# NG2092_EEPROM.net
KiCad netlist of a schematic drawn in Altium Designer
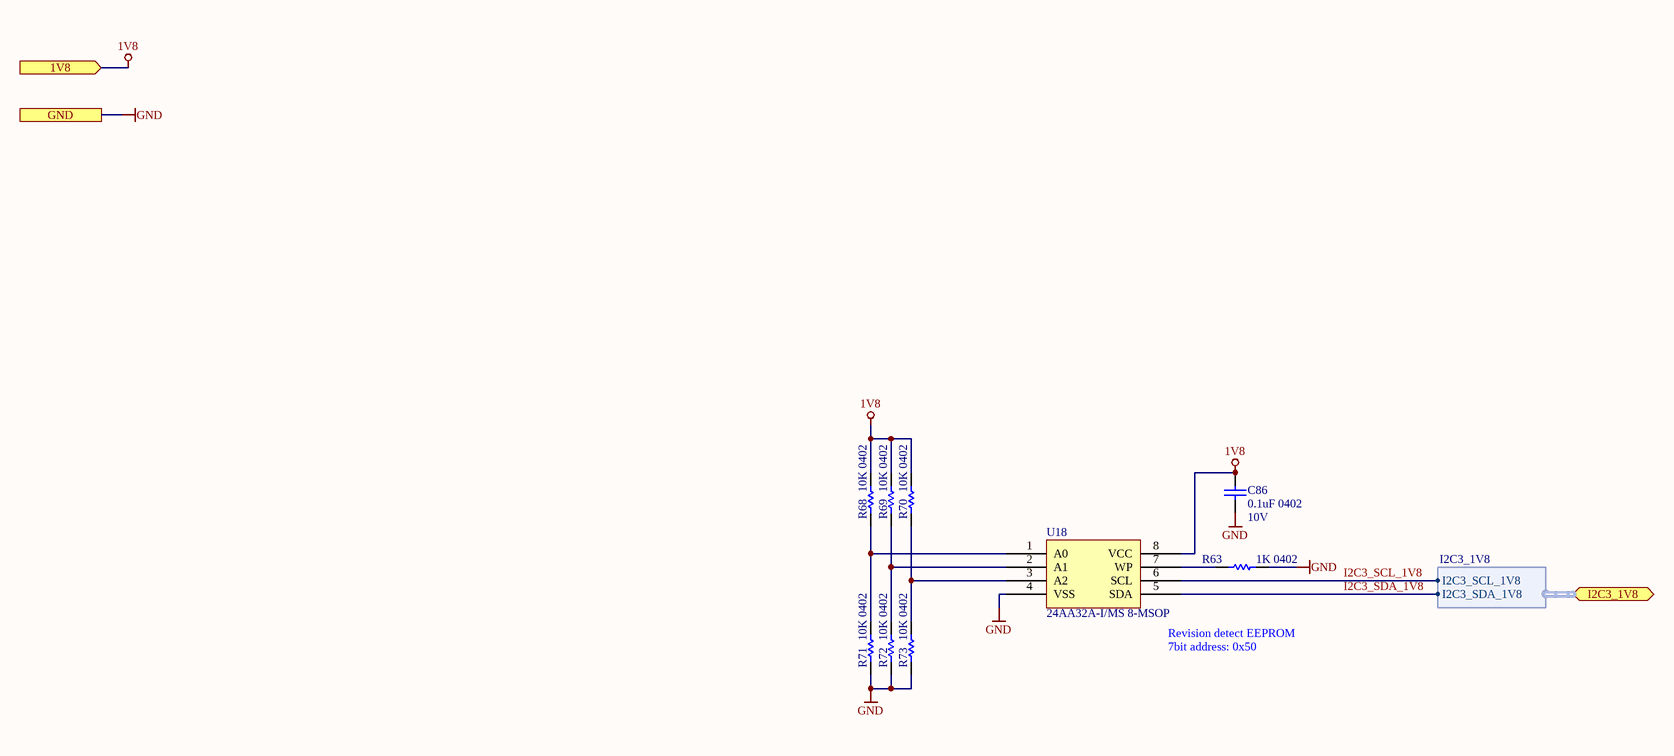
[diagram p0: NG2092_EEPROM.SchDoc]

(export (version "E")
  (design (tool "Eeschema 10.0.6"))
  (components
    (comp (ref "C86")
      (value "0.1uF 0402")
      (footprint "CAP_Altium_Vault_Generic:CAPC0402(1005)70_L")
      (description "CAP CER 0.1UF 10V X7R 0402 5%")
      (fields (field (name "TOLERANCE") "5%") (field (name "VOLTAGE RATING") "10V"))
      (libsource (lib "LuxonisMaster") (part "GRM155R71A104JA01D"))
    )
    (comp (ref "R63")
      (value "1K 0402")
      (footprint "RES_Altium_Vault_Generic:RESC0402(1005)_L")
      (description "RES SMD 1K OHM 1% 1/16W 0402")
      (fields (field (name "TOLERANCE") "1%"))
      (libsource (lib "LuxonisMaster") (part "RC0402FR-071KL"))
    )
    (comp (ref "R68")
      (value "10K 0402")
      (footprint "RES_Altium_Vault_Generic:RESC0402(1005)_L")
      (fields (field (name "TOLERANCE") "1%"))
      (libsource (lib "LuxonisMaster") (part "RC0402FR-1310KL"))
    )
    (comp (ref "R69")
      (value "10K 0402")
      (footprint "RES_Altium_Vault_Generic:RESC0402(1005)_L")
      (fields (field (name "TOLERANCE") "1%"))
      (libsource (lib "LuxonisMaster") (part "RC0402FR-1310KL"))
    )
    (comp (ref "R70")
      (value "10K 0402")
      (footprint "RES_Altium_Vault_Generic:RESC0402(1005)_L")
      (fields (field (name "TOLERANCE") "1%"))
      (libsource (lib "LuxonisMaster") (part "RC0402FR-1310KL"))
    )
    (comp (ref "R71")
      (value "10K 0402")
      (footprint "RES_Altium_Vault_Generic:RESC0402(1005)_L")
      (fields (field (name "TOLERANCE") "1%"))
      (libsource (lib "LuxonisMaster") (part "RC0402FR-1310KL"))
    )
    (comp (ref "R72")
      (value "10K 0402")
      (footprint "RES_Altium_Vault_Generic:RESC0402(1005)_L")
      (fields (field (name "TOLERANCE") "1%"))
      (libsource (lib "LuxonisMaster") (part "RC0402FR-1310KL"))
    )
    (comp (ref "R73")
      (value "10K 0402")
      (footprint "RES_Altium_Vault_Generic:RESC0402(1005)_L")
      (fields (field (name "TOLERANCE") "1%"))
      (libsource (lib "LuxonisMaster") (part "RC0402FR-1310KL"))
    )
    (comp (ref "U18")
      (value "24AA32A-I/MS 8-MSOP")
      (footprint "LuxonisMaster:24AA32A-I/MS")
      (description "IC EEPROM 32K I2C 400KHZ 8MSOP Memory IC 32Kb (4K x 8) I²C 400kHz 900ns 8-MSOP")
      (libsource (lib "LuxonisMaster") (part "24AA32A-I/MS"))
    )
  )
  (nets
    (net (code "2") (name "/I2C3_SCL_1V8") (class "Default")
      (node (ref "U18") (pin "6") (pinfunction "SCL_6") (pintype "passive"))
    )
    (net (code "3") (name "/I2C3_SDA_1V8") (class "Default")
      (node (ref "U18") (pin "5") (pinfunction "SDA_5") (pintype "passive"))
    )
    (net (code "5") (name "1V8") (class "Default")
      (node (ref "C86") (pin "2") (pinfunction "2_2") (pintype "passive"))
      (node (ref "R68") (pin "2") (pinfunction "2_2") (pintype "passive"))
      (node (ref "R69") (pin "2") (pinfunction "2_2") (pintype "passive"))
      (node (ref "R70") (pin "2") (pinfunction "2_2") (pintype "passive"))
      (node (ref "U18") (pin "8") (pinfunction "VCC_8") (pintype "passive"))
    )
    (net (code "6") (name "GND") (class "Default")
      (node (ref "C86") (pin "1") (pinfunction "1_1") (pintype "passive"))
      (node (ref "R63") (pin "1") (pinfunction "1_1") (pintype "passive"))
      (node (ref "R71") (pin "1") (pinfunction "1_1") (pintype "passive"))
      (node (ref "R72") (pin "1") (pinfunction "1_1") (pintype "passive"))
      (node (ref "R73") (pin "1") (pinfunction "1_1") (pintype "passive"))
      (node (ref "U18") (pin "4") (pinfunction "VSS_4") (pintype "passive"))
    )
    (net (code "7") (name "Net-(U18-A0)") (class "Default")
      (node (ref "R68") (pin "1") (pinfunction "1_1") (pintype "passive"))
      (node (ref "R71") (pin "2") (pinfunction "2_2") (pintype "passive"))
      (node (ref "U18") (pin "1") (pinfunction "A0_1") (pintype "passive"))
    )
    (net (code "8") (name "Net-(U18-A1)") (class "Default")
      (node (ref "R69") (pin "1") (pinfunction "1_1") (pintype "passive"))
      (node (ref "R72") (pin "2") (pinfunction "2_2") (pintype "passive"))
      (node (ref "U18") (pin "2") (pinfunction "A1_2") (pintype "passive"))
    )
    (net (code "9") (name "Net-(U18-A2)") (class "Default")
      (node (ref "R70") (pin "1") (pinfunction "1_1") (pintype "passive"))
      (node (ref "R73") (pin "2") (pinfunction "2_2") (pintype "passive"))
      (node (ref "U18") (pin "3") (pinfunction "A2_3") (pintype "passive"))
    )
    (net (code "10") (name "Net-(U18-WP)") (class "Default")
      (node (ref "R63") (pin "2") (pinfunction "2_2") (pintype "passive"))
      (node (ref "U18") (pin "7") (pinfunction "WP_7") (pintype "passive"))
    )
  )
)
